# Ecran.net
KiCad netlist of a schematic drawn in Altium Designer
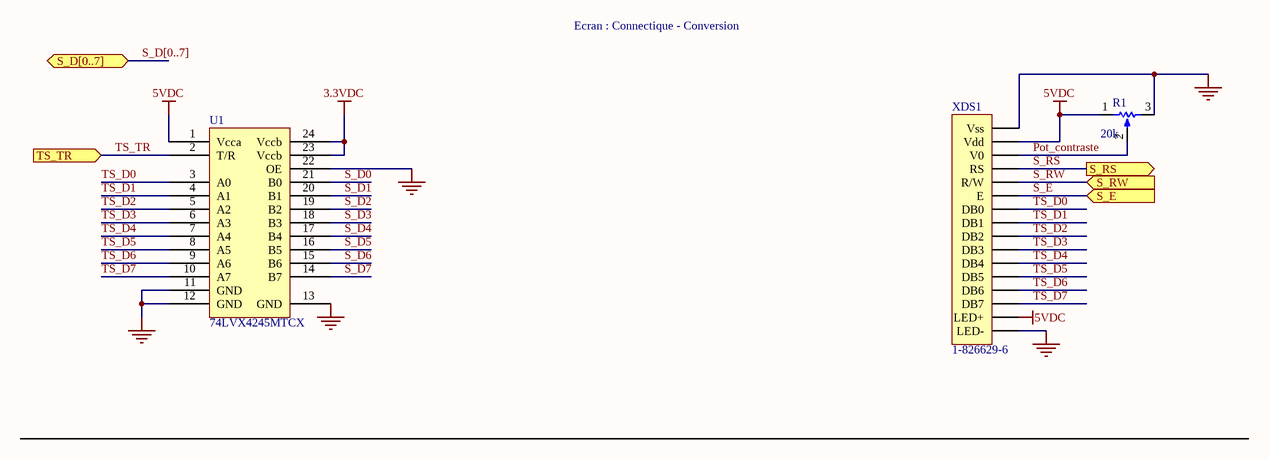
[diagram p0: Ecran.SchDoc]

(export (version "E")
  (design (tool "Eeschema 10.0.6"))
  (components
    (comp (ref "R1")
      (value "20k")
      (footprint "POTARD")
      (description "Potentiometer")
      (libsource (lib "Miscellaneous Devices") (part "RPot"))
    )
    (comp (ref "U1")
      (value "74LVX4245MTCX")
      (footprint "TRANS")
      (description "Bus Transceiver")
      (libsource (lib "Schlib1") (part "74LVX4245MTCX"))
    )
    (comp (ref "XDS1")
      (value "1-826629-6")
      (footprint "HDR1X16")
      (description "Header, 16-Pin")
      (libsource (lib "Miscellaneous Connectors") (part "Header 16"))
    )
  )
  (nets
    (net (code "1") (name "/Pot_contraste") (class "Default")
      (node (ref "R1") (pin "2") (pinfunction "TAP_2") (pintype "passive"))
      (node (ref "XDS1") (pin "3") (pinfunction "V0_3") (pintype "passive"))
    )
    (net (code "2") (name "/S_D0") (class "Default")
      (node (ref "U1") (pin "21") (pinfunction "B0_21") (pintype "passive"))
    )
    (net (code "3") (name "/S_D1") (class "Default")
      (node (ref "U1") (pin "20") (pinfunction "B1_20") (pintype "passive"))
    )
    (net (code "4") (name "/S_D2") (class "Default")
      (node (ref "U1") (pin "19") (pinfunction "B2_19") (pintype "passive"))
    )
    (net (code "5") (name "/S_D3") (class "Default")
      (node (ref "U1") (pin "18") (pinfunction "B3_18") (pintype "passive"))
    )
    (net (code "6") (name "/S_D4") (class "Default")
      (node (ref "U1") (pin "17") (pinfunction "B4_17") (pintype "passive"))
    )
    (net (code "7") (name "/S_D5") (class "Default")
      (node (ref "U1") (pin "16") (pinfunction "B5_16") (pintype "passive"))
    )
    (net (code "8") (name "/S_D6") (class "Default")
      (node (ref "U1") (pin "15") (pinfunction "B6_15") (pintype "passive"))
    )
    (net (code "9") (name "/S_D7") (class "Default")
      (node (ref "U1") (pin "14") (pinfunction "B7_14") (pintype "passive"))
    )
    (net (code "11") (name "/S_E") (class "Default")
      (node (ref "XDS1") (pin "6") (pinfunction "E_6") (pintype "passive"))
    )
    (net (code "12") (name "/S_RS") (class "Default")
      (node (ref "XDS1") (pin "4") (pinfunction "RS_4") (pintype "passive"))
    )
    (net (code "13") (name "/S_RW") (class "Default")
      (node (ref "XDS1") (pin "5") (pinfunction "R/W_5") (pintype "passive"))
    )
    (net (code "14") (name "/TS_D0") (class "Default")
      (node (ref "U1") (pin "3") (pinfunction "A0_3") (pintype "passive"))
      (node (ref "XDS1") (pin "7") (pinfunction "DB0_7") (pintype "passive"))
    )
    (net (code "15") (name "/TS_D1") (class "Default")
      (node (ref "U1") (pin "4") (pinfunction "A1_4") (pintype "passive"))
      (node (ref "XDS1") (pin "8") (pinfunction "DB1_8") (pintype "passive"))
    )
    (net (code "16") (name "/TS_D2") (class "Default")
      (node (ref "U1") (pin "5") (pinfunction "A2_5") (pintype "passive"))
      (node (ref "XDS1") (pin "9") (pinfunction "DB2_9") (pintype "passive"))
    )
    (net (code "17") (name "/TS_D3") (class "Default")
      (node (ref "U1") (pin "6") (pinfunction "A3_6") (pintype "passive"))
      (node (ref "XDS1") (pin "10") (pinfunction "DB3_10") (pintype "passive"))
    )
    (net (code "18") (name "/TS_D4") (class "Default")
      (node (ref "U1") (pin "7") (pinfunction "A4_7") (pintype "passive"))
      (node (ref "XDS1") (pin "11") (pinfunction "DB4_11") (pintype "passive"))
    )
    (net (code "19") (name "/TS_D5") (class "Default")
      (node (ref "U1") (pin "8") (pinfunction "A5_8") (pintype "passive"))
      (node (ref "XDS1") (pin "12") (pinfunction "DB5_12") (pintype "passive"))
    )
    (net (code "20") (name "/TS_D6") (class "Default")
      (node (ref "U1") (pin "9") (pinfunction "A6_9") (pintype "passive"))
      (node (ref "XDS1") (pin "13") (pinfunction "DB6_13") (pintype "passive"))
    )
    (net (code "21") (name "/TS_D7") (class "Default")
      (node (ref "U1") (pin "10") (pinfunction "A7_10") (pintype "passive"))
      (node (ref "XDS1") (pin "14") (pinfunction "DB7_14") (pintype "passive"))
    )
    (net (code "22") (name "/TS_TR") (class "Default")
      (node (ref "U1") (pin "2") (pinfunction "T/R_2") (pintype "passive"))
    )
    (net (code "23") (name "3.3VDC") (class "Default")
      (node (ref "U1") (pin "23") (pinfunction "Vccb_23") (pintype "passive"))
      (node (ref "U1") (pin "24") (pinfunction "Vccb_24") (pintype "passive"))
    )
    (net (code "24") (name "5VDC") (class "Default")
      (node (ref "R1") (pin "1") (pinfunction "TOP_1") (pintype "passive"))
      (node (ref "U1") (pin "1") (pinfunction "Vcca_1") (pintype "passive"))
      (node (ref "XDS1") (pin "15") (pinfunction "LED+_15") (pintype "passive"))
      (node (ref "XDS1") (pin "2") (pinfunction "Vdd_2") (pintype "passive"))
    )
    (net (code "25") (name "GND") (class "Default")
      (node (ref "R1") (pin "3") (pinfunction "BOT_3") (pintype "passive"))
      (node (ref "U1") (pin "11") (pinfunction "GND_11") (pintype "passive"))
      (node (ref "U1") (pin "12") (pinfunction "GND_12") (pintype "passive"))
      (node (ref "U1") (pin "13") (pinfunction "GND_13") (pintype "passive"))
      (node (ref "U1") (pin "22") (pinfunction "OE_22") (pintype "passive"))
      (node (ref "XDS1") (pin "1") (pinfunction "Vss_1") (pintype "passive"))
      (node (ref "XDS1") (pin "16") (pinfunction "LED-_16") (pintype "passive"))
    )
  )
)
